# Adafruit_I2S_Mic_SPK0415HM4H.net
KiCad netlist of a schematic drawn in EAGLE
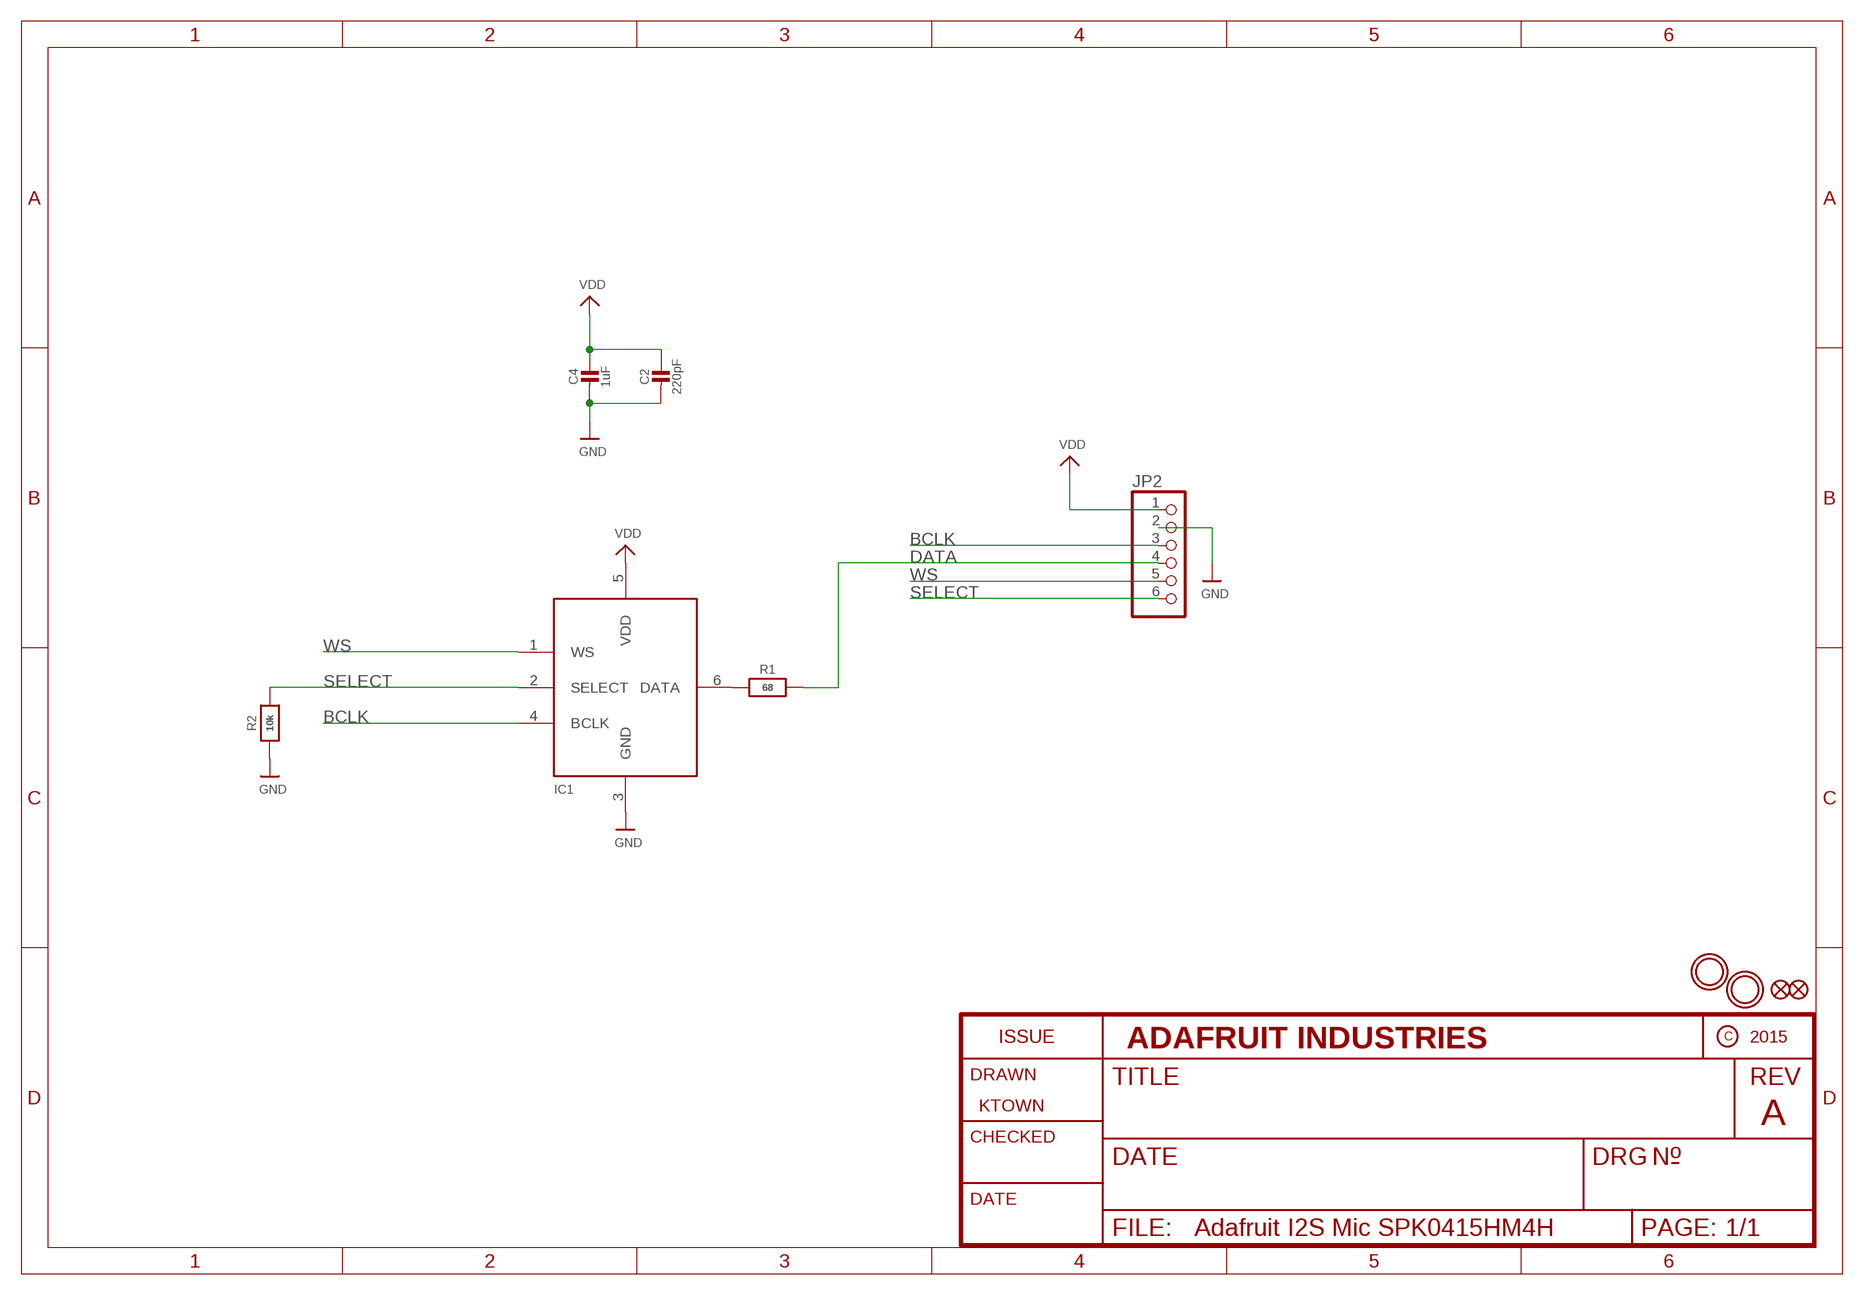
[diagram p0: schematic, sheet 1]

(export (version "E")
  (design (tool "Eeschema 10.0.6"))
  (components
    (comp (ref "C2")
      (value "220pF")
      (footprint "eagle-import:0805-NO")
      (libsource (lib "eagle-import") (part "CAP_CERAMIC0805-NOOUTLINE"))
    )
    (comp (ref "C4")
      (value "1uF")
      (footprint "eagle-import:0805-NO")
      (libsource (lib "eagle-import") (part "CAP_CERAMIC0805-NOOUTLINE"))
    )
    (comp (ref "FID1")
      (value "FIDUCIAL_1MM")
      (footprint "eagle-import:FIDUCIAL_1MM")
      (libsource (lib "eagle-import") (part "FIDUCIAL_1MM"))
    )
    (comp (ref "FID2")
      (value "FIDUCIAL_1MM")
      (footprint "eagle-import:FIDUCIAL_1MM")
      (libsource (lib "eagle-import") (part "FIDUCIAL_1MM"))
    )
    (comp (ref "IC1")
      (value "MIC_I2S_SPH0645")
      (footprint "eagle-import:SPH0645LM4H")
      (libsource (lib "eagle-import") (part "MIC_I2S_SPH0645"))
    )
    (comp (ref "JP2")
      (value "HEADER-1X6ROUND")
      (footprint "eagle-import:1X06_ROUND")
      (libsource (lib "eagle-import") (part "HEADER-1X6ROUND"))
    )
    (comp (ref "R1")
      (value "68")
      (footprint "eagle-import:0603-NO")
      (libsource (lib "eagle-import") (part "RESISTOR_0603_NOOUT"))
    )
    (comp (ref "R2")
      (value "10k")
      (footprint "eagle-import:0603-NO")
      (libsource (lib "eagle-import") (part "RESISTOR_0603_NOOUT"))
    )
    (comp (ref "U$6")
      (value "MOUNTINGHOLE2.5")
      (footprint "eagle-import:MOUNTINGHOLE_2.5_PLATED")
      (libsource (lib "eagle-import") (part "MOUNTINGHOLE2.5"))
    )
    (comp (ref "U$12")
      (value "MOUNTINGHOLE2.5")
      (footprint "eagle-import:MOUNTINGHOLE_2.5_PLATED")
      (libsource (lib "eagle-import") (part "MOUNTINGHOLE2.5"))
    )
  )
  (nets
    (net (code "1") (name "/BCLK") (class "Default")
      (node (ref "IC1") (pin "4") (pinfunction "BCLK_4") (pintype "input"))
      (node (ref "JP2") (pin "3") (pinfunction "3_3") (pintype "passive"))
    )
    (net (code "2") (name "/DATA") (class "Default")
      (node (ref "JP2") (pin "4") (pinfunction "4_4") (pintype "passive"))
      (node (ref "R1") (pin "2") (pinfunction "2_2") (pintype "passive"))
    )
    (net (code "3") (name "/SELECT") (class "Default")
      (node (ref "IC1") (pin "2") (pinfunction "SELECT_2") (pintype "input"))
      (node (ref "JP2") (pin "6") (pinfunction "6_6") (pintype "passive"))
      (node (ref "R2") (pin "2") (pinfunction "2_2") (pintype "passive"))
    )
    (net (code "4") (name "/WS") (class "Default")
      (node (ref "IC1") (pin "1") (pinfunction "WS_1") (pintype "input"))
      (node (ref "JP2") (pin "5") (pinfunction "5_5") (pintype "passive"))
    )
    (net (code "5") (name "GND") (class "Default")
      (node (ref "C2") (pin "2") (pinfunction "2_2") (pintype "passive"))
      (node (ref "C4") (pin "2") (pinfunction "2_2") (pintype "passive"))
      (node (ref "IC1") (pin "3") (pinfunction "GND_3") (pintype "power_in"))
      (node (ref "JP2") (pin "2") (pinfunction "2_2") (pintype "passive"))
      (node (ref "R2") (pin "1") (pinfunction "1_1") (pintype "passive"))
    )
    (net (code "6") (name "Net-(IC1-DATA)") (class "Default")
      (node (ref "IC1") (pin "6") (pinfunction "DATA_6") (pintype "output"))
      (node (ref "R1") (pin "1") (pinfunction "1_1") (pintype "passive"))
    )
    (net (code "7") (name "VDD") (class "Default")
      (node (ref "C2") (pin "1") (pinfunction "1_1") (pintype "passive"))
      (node (ref "C4") (pin "1") (pinfunction "1_1") (pintype "passive"))
      (node (ref "IC1") (pin "5") (pinfunction "VDD_5") (pintype "power_in"))
      (node (ref "JP2") (pin "1") (pinfunction "1_1") (pintype "passive"))
    )
  )
)
